# 25062016wearable_v1_1.net
KiCad netlist of a schematic drawn in EAGLE
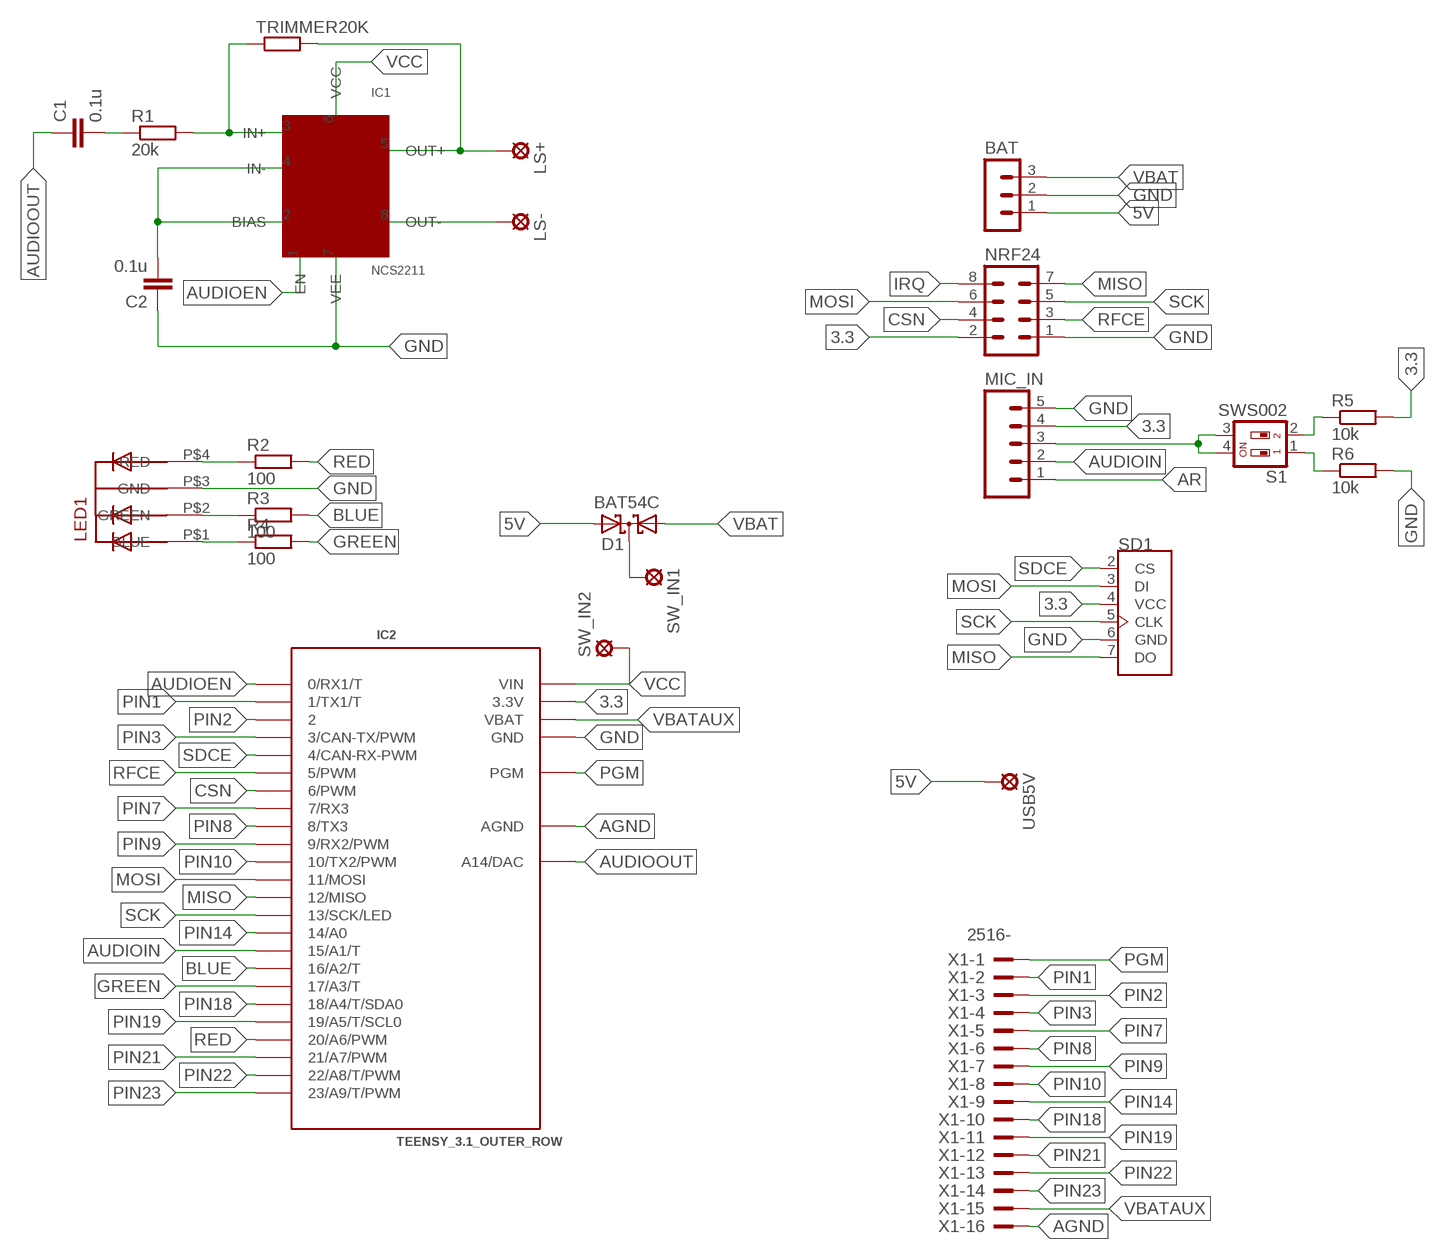
[diagram p0: schematic, sheet 1]

(export (version "E")
  (design (tool "Eeschema 10.0.6"))
  (components
    (comp (ref "BAT")
      (value "MA03-1")
      (footprint "eagle-import:MA03-1")
      (libsource (lib "eagle-import") (part "MA03-1"))
    )
    (comp (ref "C1")
      (value "0.1u")
      (footprint "eagle-import:C2.5-2")
      (libsource (lib "eagle-import") (part "C2.5/2"))
    )
    (comp (ref "C2")
      (value "0.1u")
      (footprint "eagle-import:C2.5-2")
      (libsource (lib "eagle-import") (part "C2.5/2"))
    )
    (comp (ref "D1")
      (value "BAT54C")
      (footprint "eagle-import:SOT23")
      (libsource (lib "eagle-import") (part "BAT54C"))
    )
    (comp (ref "IC1")
      (value "NCS2211")
      (footprint "eagle-import:SOIC-8")
      (libsource (lib "eagle-import") (part "NCS2211"))
    )
    (comp (ref "IC2")
      (value "TEENSY_3.1_OUTER_ROW")
      (footprint "eagle-import:TEENSY3-OUTER_ROW")
      (libsource (lib "eagle-import") (part "TEENSY_3.1_OUTER_ROW"))
    )
    (comp (ref "LED1")
      (value "5MMRGBLED")
      (footprint "eagle-import:LED5MMRGB")
      (libsource (lib "eagle-import") (part "5MMRGBLED"))
    )
    (comp (ref "LS+")
      (value "LSP10")
      (footprint "eagle-import:LSP10")
      (libsource (lib "eagle-import") (part "LSP10"))
    )
    (comp (ref "LS-")
      (value "LSP10")
      (footprint "eagle-import:LSP10")
      (libsource (lib "eagle-import") (part "LSP10"))
    )
    (comp (ref "MIC_IN")
      (value "MA05")
      (footprint "eagle-import:05PA")
      (libsource (lib "eagle-import") (part "MA05"))
    )
    (comp (ref "NRF24")
      (value "MA04-2")
      (footprint "eagle-import:MA04-2")
      (libsource (lib "eagle-import") (part "MA04-2"))
    )
    (comp (ref "R1")
      (value "20k")
      (footprint "eagle-import:0204_7")
      (libsource (lib "eagle-import") (part "R-EU_0204/7"))
    )
    (comp (ref "R2")
      (value "100")
      (footprint "eagle-import:0207_2V")
      (libsource (lib "eagle-import") (part "R-EU_0207/2V"))
    )
    (comp (ref "R3")
      (value "100")
      (footprint "eagle-import:0207_2V")
      (libsource (lib "eagle-import") (part "R-EU_0207/2V"))
    )
    (comp (ref "R4")
      (value "100")
      (footprint "eagle-import:0207_2V")
      (libsource (lib "eagle-import") (part "R-EU_0207/2V"))
    )
    (comp (ref "R5")
      (value "10k")
      (footprint "eagle-import:0207_2V")
      (libsource (lib "eagle-import") (part "R-EU_0207/2V"))
    )
    (comp (ref "R6")
      (value "10k")
      (footprint "eagle-import:0207_2V")
      (libsource (lib "eagle-import") (part "R-EU_0207/2V"))
    )
    (comp (ref "S1")
      (value "SWS002")
      (footprint "eagle-import:SMS-002")
      (libsource (lib "eagle-import") (part "SWS002"))
    )
    (comp (ref "SD1")
      (value "MICROSD_SF-MICROSD")
      (footprint "eagle-import:MICROSD_MICROSD")
      (libsource (lib "eagle-import") (part "MICROSD_SF-MICROSD"))
    )
    (comp (ref "SW_IN1")
      (value "SE11")
      (footprint "eagle-import:SE11")
      (libsource (lib "eagle-import") (part "SE11"))
    )
    (comp (ref "SW_IN2")
      (value "SE11")
      (footprint "eagle-import:SE11")
      (libsource (lib "eagle-import") (part "SE11"))
    )
    (comp (ref "TRIMMER20K")
      (value "R-EU_0207/2V")
      (footprint "eagle-import:0207_2V")
      (libsource (lib "eagle-import") (part "R-EU_0207/2V"))
    )
    (comp (ref "USB5V")
      (value "LSP10")
      (footprint "eagle-import:LSP10")
      (libsource (lib "eagle-import") (part "LSP10"))
    )
    (comp (ref "X1")
      (value "2516-")
      (footprint "eagle-import:PAK100_2500-16")
      (libsource (lib "eagle-import") (part "2516-"))
    )
  )
  (nets
    (net (code "1") (name "3.3") (class "Default")
      (node (ref "IC2") (pin "3.3V") (pinfunction "3.3V_3.3V") (pintype "power_in"))
      (node (ref "IC2") (pin "3.3V1") (pinfunction "3.3V_3.3V1") (pintype "power_in"))
      (node (ref "MIC_IN") (pin "4") (pinfunction "4_4") (pintype "passive"))
      (node (ref "NRF24") (pin "2") (pinfunction "2_2") (pintype "passive"))
      (node (ref "R5") (pin "2") (pinfunction "2_2") (pintype "passive"))
      (node (ref "SD1") (pin "4") (pinfunction "VCC_4") (pintype "power_in"))
    )
    (net (code "2") (name "5V") (class "Default")
      (node (ref "BAT") (pin "1") (pinfunction "1_1") (pintype "passive"))
      (node (ref "D1") (pin "2") (pinfunction "A2_2") (pintype "passive"))
      (node (ref "USB5V") (pin "MP") (pinfunction "MP_MP") (pintype "passive"))
    )
    (net (code "3") (name "AGND") (class "Default")
      (node (ref "IC2") (pin "AGND") (pinfunction "AGND_AGND") (pintype "power_in"))
      (node (ref "X1") (pin "16") (pinfunction "KL_16") (pintype "passive"))
    )
    (net (code "4") (name "AR") (class "Default")
      (node (ref "MIC_IN") (pin "1") (pinfunction "1_1") (pintype "passive"))
    )
    (net (code "5") (name "AUDIOEN") (class "Default")
      (node (ref "IC1") (pin "1") (pinfunction "EN_1") (pintype "bidirectional"))
      (node (ref "IC2") (pin "0") (pinfunction "0/RX1/T_0") (pintype "bidirectional"))
    )
    (net (code "6") (name "AUDIOIN") (class "Default")
      (node (ref "IC2") (pin "15/A1") (pinfunction "15/A1/T_15/A1") (pintype "bidirectional"))
      (node (ref "MIC_IN") (pin "2") (pinfunction "2_2") (pintype "passive"))
    )
    (net (code "7") (name "AUDIOOUT") (class "Default")
      (node (ref "C1") (pin "1") (pinfunction "1_1") (pintype "passive"))
      (node (ref "IC2") (pin "RESET/DAC") (pinfunction "A14/DAC_RESET/DAC") (pintype "bidirectional"))
    )
    (net (code "8") (name "BLUE") (class "Default")
      (node (ref "IC2") (pin "16/A2") (pinfunction "16/A2/T_16/A2") (pintype "bidirectional"))
      (node (ref "R3") (pin "2") (pinfunction "2_2") (pintype "passive"))
    )
    (net (code "9") (name "CSN") (class "Default")
      (node (ref "IC2") (pin "6") (pinfunction "6/PWM_6") (pintype "bidirectional"))
      (node (ref "NRF24") (pin "4") (pinfunction "4_4") (pintype "passive"))
    )
    (net (code "10") (name "GND") (class "Default")
      (node (ref "BAT") (pin "2") (pinfunction "2_2") (pintype "passive"))
      (node (ref "C2") (pin "1") (pinfunction "1_1") (pintype "passive"))
      (node (ref "IC1") (pin "7") (pinfunction "VEE_7") (pintype "bidirectional"))
      (node (ref "IC2") (pin "GND") (pinfunction "GND_GND") (pintype "power_in"))
      (node (ref "IC2") (pin "GND1") (pinfunction "GND_GND1") (pintype "power_in"))
      (node (ref "LED1") (pin "P$3") (pinfunction "GND_P$3") (pintype "bidirectional"))
      (node (ref "MIC_IN") (pin "5") (pinfunction "5_5") (pintype "passive"))
      (node (ref "NRF24") (pin "1") (pinfunction "1_1") (pintype "passive"))
      (node (ref "R6") (pin "2") (pinfunction "2_2") (pintype "passive"))
      (node (ref "SD1") (pin "6") (pinfunction "GND_6") (pintype "power_in"))
    )
    (net (code "11") (name "GREEN") (class "Default")
      (node (ref "IC2") (pin "17/A3") (pinfunction "17/A3/T_17/A3") (pintype "bidirectional"))
      (node (ref "R4") (pin "2") (pinfunction "2_2") (pintype "passive"))
    )
    (net (code "12") (name "IRQ") (class "Default")
      (node (ref "NRF24") (pin "8") (pinfunction "8_8") (pintype "passive"))
    )
    (net (code "13") (name "MISO") (class "Default")
      (node (ref "IC2") (pin "12") (pinfunction "12/MISO_12") (pintype "bidirectional"))
      (node (ref "NRF24") (pin "7") (pinfunction "7_7") (pintype "passive"))
      (node (ref "SD1") (pin "7") (pinfunction "DO_7") (pintype "output"))
    )
    (net (code "14") (name "MOSI") (class "Default")
      (node (ref "IC2") (pin "11") (pinfunction "11/MOSI_11") (pintype "bidirectional"))
      (node (ref "NRF24") (pin "6") (pinfunction "6_6") (pintype "passive"))
      (node (ref "SD1") (pin "3") (pinfunction "DI_3") (pintype "input"))
    )
    (net (code "15") (name "Net-(C1-Pad2)") (class "Default")
      (node (ref "C1") (pin "2") (pinfunction "2_2") (pintype "passive"))
      (node (ref "R1") (pin "1") (pinfunction "1_1") (pintype "passive"))
    )
    (net (code "16") (name "Net-(D1-CC)") (class "Default")
      (node (ref "D1") (pin "3") (pinfunction "CC_3") (pintype "passive"))
      (node (ref "SW_IN1") (pin "MP") (pinfunction "MP_MP") (pintype "passive"))
    )
    (net (code "17") (name "Net-(IC1-BIAS)") (class "Default")
      (node (ref "C2") (pin "2") (pinfunction "2_2") (pintype "passive"))
      (node (ref "IC1") (pin "2") (pinfunction "BIAS_2") (pintype "bidirectional"))
      (node (ref "IC1") (pin "4") (pinfunction "IN-_4") (pintype "bidirectional"))
    )
    (net (code "18") (name "Net-(IC1-IN+)") (class "Default")
      (node (ref "IC1") (pin "3") (pinfunction "IN+_3") (pintype "bidirectional"))
      (node (ref "R1") (pin "2") (pinfunction "2_2") (pintype "passive"))
      (node (ref "TRIMMER20K") (pin "1") (pinfunction "1_1") (pintype "passive"))
    )
    (net (code "19") (name "Net-(IC1-OUT+)") (class "Default")
      (node (ref "IC1") (pin "5") (pinfunction "OUT+_5") (pintype "bidirectional"))
      (node (ref "LS+") (pin "MP") (pinfunction "MP_MP") (pintype "passive"))
      (node (ref "TRIMMER20K") (pin "2") (pinfunction "2_2") (pintype "passive"))
    )
    (net (code "20") (name "Net-(IC1-OUT-)") (class "Default")
      (node (ref "IC1") (pin "8") (pinfunction "OUT-_8") (pintype "bidirectional"))
      (node (ref "LS-") (pin "MP") (pinfunction "MP_MP") (pintype "passive"))
    )
    (net (code "21") (name "Net-(LED1-BLUE)") (class "Default")
      (node (ref "LED1") (pin "P$1") (pinfunction "BLUE_P$1") (pintype "bidirectional"))
      (node (ref "R4") (pin "1") (pinfunction "1_1") (pintype "passive"))
    )
    (net (code "22") (name "Net-(LED1-GREEN)") (class "Default")
      (node (ref "LED1") (pin "P$2") (pinfunction "GREEN_P$2") (pintype "bidirectional"))
      (node (ref "R3") (pin "1") (pinfunction "1_1") (pintype "passive"))
    )
    (net (code "23") (name "Net-(LED1-RED)") (class "Default")
      (node (ref "LED1") (pin "P$4") (pinfunction "RED_P$4") (pintype "bidirectional"))
      (node (ref "R2") (pin "1") (pinfunction "1_1") (pintype "passive"))
    )
    (net (code "24") (name "Net-(MIC_IN-Pad3)") (class "Default")
      (node (ref "MIC_IN") (pin "3") (pinfunction "3_3") (pintype "passive"))
      (node (ref "S1") (pin "3") (pinfunction "3_3") (pintype "passive"))
      (node (ref "S1") (pin "4") (pinfunction "4_4") (pintype "passive"))
    )
    (net (code "25") (name "Net-(R5-Pad1)") (class "Default")
      (node (ref "R5") (pin "1") (pinfunction "1_1") (pintype "passive"))
      (node (ref "S1") (pin "2") (pinfunction "2_2") (pintype "passive"))
    )
    (net (code "26") (name "Net-(R6-Pad1)") (class "Default")
      (node (ref "R6") (pin "1") (pinfunction "1_1") (pintype "passive"))
      (node (ref "S1") (pin "1") (pinfunction "1_1") (pintype "passive"))
    )
    (net (code "27") (name "PGM") (class "Default")
      (node (ref "IC2") (pin "PGM") (pinfunction "PGM_PGM") (pintype "bidirectional"))
      (node (ref "X1") (pin "1") (pinfunction "KL_1") (pintype "passive"))
    )
    (net (code "28") (name "PIN1") (class "Default")
      (node (ref "IC2") (pin "1") (pinfunction "1/TX1/T_1") (pintype "bidirectional"))
      (node (ref "X1") (pin "2") (pinfunction "KL_2") (pintype "passive"))
    )
    (net (code "29") (name "PIN2") (class "Default")
      (node (ref "IC2") (pin "2") (pinfunction "2_2") (pintype "bidirectional"))
      (node (ref "X1") (pin "3") (pinfunction "KL_3") (pintype "passive"))
    )
    (net (code "30") (name "PIN3") (class "Default")
      (node (ref "IC2") (pin "3") (pinfunction "3/CAN-TX/PWM_3") (pintype "bidirectional"))
      (node (ref "X1") (pin "4") (pinfunction "KL_4") (pintype "passive"))
    )
    (net (code "31") (name "PIN7") (class "Default")
      (node (ref "IC2") (pin "7") (pinfunction "7/RX3_7") (pintype "bidirectional"))
      (node (ref "X1") (pin "5") (pinfunction "KL_5") (pintype "passive"))
    )
    (net (code "32") (name "PIN8") (class "Default")
      (node (ref "IC2") (pin "8") (pinfunction "8/TX3_8") (pintype "bidirectional"))
      (node (ref "X1") (pin "6") (pinfunction "KL_6") (pintype "passive"))
    )
    (net (code "33") (name "PIN9") (class "Default")
      (node (ref "IC2") (pin "9") (pinfunction "9/RX2/PWM_9") (pintype "bidirectional"))
      (node (ref "X1") (pin "7") (pinfunction "KL_7") (pintype "passive"))
    )
    (net (code "34") (name "PIN10") (class "Default")
      (node (ref "IC2") (pin "10") (pinfunction "10/TX2/PWM_10") (pintype "bidirectional"))
      (node (ref "X1") (pin "8") (pinfunction "KL_8") (pintype "passive"))
    )
    (net (code "35") (name "PIN14") (class "Default")
      (node (ref "IC2") (pin "14/A0") (pinfunction "14/A0_14/A0") (pintype "bidirectional"))
      (node (ref "X1") (pin "9") (pinfunction "KL_9") (pintype "passive"))
    )
    (net (code "36") (name "PIN18") (class "Default")
      (node (ref "IC2") (pin "18/A4") (pinfunction "18/A4/T/SDA0_18/A4") (pintype "bidirectional"))
      (node (ref "X1") (pin "10") (pinfunction "KL_10") (pintype "passive"))
    )
    (net (code "37") (name "PIN19") (class "Default")
      (node (ref "IC2") (pin "19/A5") (pinfunction "19/A5/T/SCL0_19/A5") (pintype "bidirectional"))
      (node (ref "X1") (pin "11") (pinfunction "KL_11") (pintype "passive"))
    )
    (net (code "38") (name "PIN21") (class "Default")
      (node (ref "IC2") (pin "21/A7") (pinfunction "21/A7/PWM_21/A7") (pintype "bidirectional"))
      (node (ref "X1") (pin "12") (pinfunction "KL_12") (pintype "passive"))
    )
    (net (code "39") (name "PIN22") (class "Default")
      (node (ref "IC2") (pin "22/A8") (pinfunction "22/A8/T/PWM_22/A8") (pintype "bidirectional"))
      (node (ref "X1") (pin "13") (pinfunction "KL_13") (pintype "passive"))
    )
    (net (code "40") (name "PIN23") (class "Default")
      (node (ref "IC2") (pin "23/A9") (pinfunction "23/A9/T/PWM_23/A9") (pintype "bidirectional"))
      (node (ref "X1") (pin "14") (pinfunction "KL_14") (pintype "passive"))
    )
    (net (code "41") (name "RED") (class "Default")
      (node (ref "IC2") (pin "20/A6") (pinfunction "20/A6/PWM_20/A6") (pintype "bidirectional"))
      (node (ref "R2") (pin "2") (pinfunction "2_2") (pintype "passive"))
    )
    (net (code "42") (name "RFCE") (class "Default")
      (node (ref "IC2") (pin "5") (pinfunction "5/PWM_5") (pintype "bidirectional"))
      (node (ref "NRF24") (pin "3") (pinfunction "3_3") (pintype "passive"))
    )
    (net (code "43") (name "SCK") (class "Default")
      (node (ref "IC2") (pin "13") (pinfunction "13/SCK/LED_13") (pintype "bidirectional"))
      (node (ref "NRF24") (pin "5") (pinfunction "5_5") (pintype "passive"))
      (node (ref "SD1") (pin "5") (pinfunction "CLK_5") (pintype "input"))
    )
    (net (code "44") (name "SDCE") (class "Default")
      (node (ref "IC2") (pin "4") (pinfunction "4/CAN-RX-PWM_4") (pintype "bidirectional"))
      (node (ref "SD1") (pin "2") (pinfunction "CS_2") (pintype "input"))
    )
    (net (code "45") (name "VBAT") (class "Default")
      (node (ref "BAT") (pin "3") (pinfunction "3_3") (pintype "passive"))
      (node (ref "D1") (pin "1") (pinfunction "A1_1") (pintype "passive"))
    )
    (net (code "46") (name "VBATAUX") (class "Default")
      (node (ref "IC2") (pin "VBAT") (pinfunction "VBAT_VBAT") (pintype "power_in"))
      (node (ref "X1") (pin "15") (pinfunction "KL_15") (pintype "passive"))
    )
    (net (code "47") (name "VCC") (class "Default")
      (node (ref "IC1") (pin "6") (pinfunction "VCC_6") (pintype "bidirectional"))
      (node (ref "IC2") (pin "VIN") (pinfunction "VIN_VIN") (pintype "power_in"))
      (node (ref "SW_IN2") (pin "MP") (pinfunction "MP_MP") (pintype "passive"))
    )
  )
)
